# cpu2_lock_comm.net
KiCad netlist of a schematic drawn in Altium Designer
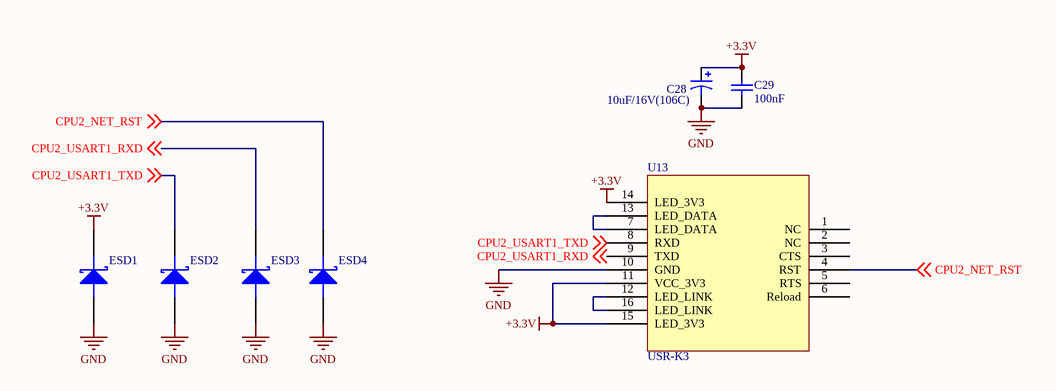
[diagram p0: cpu2_lock_comm.SchDoc]

(export (version "E")
  (design (tool "Eeschema 10.0.6"))
  (components
    (comp (ref "C28")
      (value "10uF/16V(106C)")
      (footprint "CAP A-3216")
      (description "Polarized Capacitor (Surface Mount)")
      (fields (field (name "Comment") "Cap Pol3") (field (name "PUBLISHER") "Altium Limited"))
      (libsource (lib "Miscellaneous Devices") (part "Cap Pol3"))
    )
    (comp (ref "C29")
      (value "100nF")
      (footprint "0805_C")
      (description "贴片电容")
      (libsource (lib "Miscellaneous Devices LC") (part "0805 100nF(104) 10% 50V"))
    )
    (comp (ref "ESD1")
      (value "ESD5B5.0ST1G")
      (footprint "SOD-523")
      (libsource (lib "myIntegrated_Library1") (part "ESD5B5.0ST1G"))
    )
    (comp (ref "ESD2")
      (value "ESD5B5.0ST1G")
      (footprint "SOD-523")
      (libsource (lib "myIntegrated_Library1") (part "ESD5B5.0ST1G"))
    )
    (comp (ref "ESD3")
      (value "ESD5B5.0ST1G")
      (footprint "SOD-523")
      (libsource (lib "myIntegrated_Library1") (part "ESD5B5.0ST1G"))
    )
    (comp (ref "ESD4")
      (value "ESD5B5.0ST1G")
      (footprint "SOD-523")
      (libsource (lib "myIntegrated_Library1") (part "ESD5B5.0ST1G"))
    )
    (comp (ref "U13")
      (value "USR-K3")
      (footprint "USR-K3")
      (libsource (lib "myIntegrated_Library1") (part "USR-K3"))
    )
  )
  (nets
    (net (code "1") (name "+3.3V") (class "Default")
      (node (ref "C28") (pin "1") (pinfunction "1_1") (pintype "passive"))
      (node (ref "C29") (pin "2") (pinfunction "2_2") (pintype "passive"))
      (node (ref "ESD1") (pin "2") (pinfunction "2_2") (pintype "passive"))
      (node (ref "U13") (pin "11") (pinfunction "VCC_3V3_11") (pintype "passive"))
      (node (ref "U13") (pin "14") (pinfunction "LED_3V3_14") (pintype "passive"))
      (node (ref "U13") (pin "15") (pinfunction "LED_3V3_15") (pintype "passive"))
    )
    (net (code "2") (name "CPU2_NET_RST") (class "Default")
      (node (ref "ESD4") (pin "2") (pinfunction "2_2") (pintype "passive"))
      (node (ref "U13") (pin "4") (pinfunction "RST_4") (pintype "passive"))
    )
    (net (code "3") (name "CPU2_USART1_RXD") (class "Default")
      (node (ref "ESD3") (pin "2") (pinfunction "2_2") (pintype "passive"))
      (node (ref "U13") (pin "9") (pinfunction "TXD_9") (pintype "passive"))
    )
    (net (code "4") (name "CPU2_USART1_TXD") (class "Default")
      (node (ref "ESD2") (pin "2") (pinfunction "2_2") (pintype "passive"))
      (node (ref "U13") (pin "8") (pinfunction "RXD_8") (pintype "passive"))
    )
    (net (code "5") (name "GND") (class "Default")
      (node (ref "C28") (pin "2") (pinfunction "2_2") (pintype "passive"))
      (node (ref "C29") (pin "1") (pinfunction "1_1") (pintype "passive"))
      (node (ref "ESD1") (pin "1") (pinfunction "1_1") (pintype "passive"))
      (node (ref "ESD2") (pin "1") (pinfunction "1_1") (pintype "passive"))
      (node (ref "ESD3") (pin "1") (pinfunction "1_1") (pintype "passive"))
      (node (ref "ESD4") (pin "1") (pinfunction "1_1") (pintype "passive"))
      (node (ref "U13") (pin "10") (pinfunction "GND_10") (pintype "passive"))
    )
    (net (code "6") (name "Net-(U13-LED_DATA-Pad13)") (class "Default")
      (node (ref "U13") (pin "13") (pinfunction "LED_DATA_13") (pintype "passive"))
      (node (ref "U13") (pin "7") (pinfunction "LED_DATA_7") (pintype "passive"))
    )
    (net (code "7") (name "Net-(U13-LED_LINK-Pad12)") (class "Default")
      (node (ref "U13") (pin "12") (pinfunction "LED_LINK_12") (pintype "passive"))
      (node (ref "U13") (pin "16") (pinfunction "LED_LINK_16") (pintype "passive"))
    )
    (net (code "8") (name "unconnected-(U13-CTS-Pad3)") (class "Default")
      (node (ref "U13") (pin "3") (pinfunction "CTS_3") (pintype "passive"))
    )
    (net (code "9") (name "unconnected-(U13-NC-Pad1)") (class "Default")
      (node (ref "U13") (pin "1") (pinfunction "NC_1") (pintype "passive"))
    )
    (net (code "10") (name "unconnected-(U13-NC-Pad2)") (class "Default")
      (node (ref "U13") (pin "2") (pinfunction "NC_2") (pintype "passive"))
    )
    (net (code "11") (name "unconnected-(U13-RTS-Pad5)") (class "Default")
      (node (ref "U13") (pin "5") (pinfunction "RTS_5") (pintype "passive"))
    )
    (net (code "12") (name "unconnected-(U13-Reload-Pad6)") (class "Default")
      (node (ref "U13") (pin "6") (pinfunction "Reload_6") (pintype "passive"))
    )
  )
)
